# FTDI_Breakoput_Board.net
KiCad netlist of a schematic drawn in EAGLE
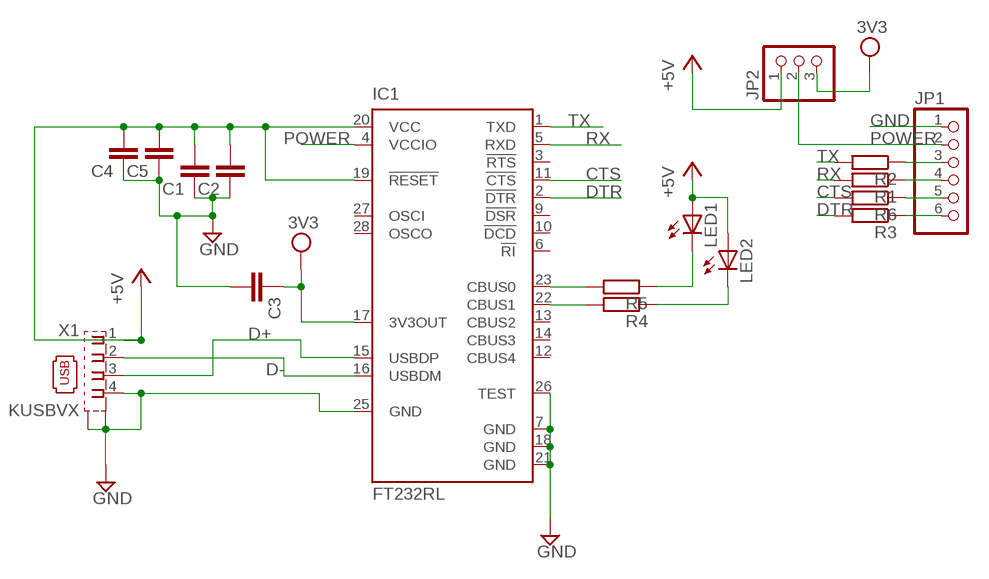
[diagram p0: schematic, sheet 1]

(export (version "E")
  (design (tool "Eeschema 10.0.6"))
  (components
    (comp (ref "C1")
      (value "C-EUC0805")
      (footprint "eagle-import:C0805")
      (libsource (lib "eagle-import") (part "C-EUC0805"))
    )
    (comp (ref "C2")
      (value "C-EUC0805")
      (footprint "eagle-import:C0805")
      (libsource (lib "eagle-import") (part "C-EUC0805"))
    )
    (comp (ref "C3")
      (value "C-EUC0805")
      (footprint "eagle-import:C0805")
      (libsource (lib "eagle-import") (part "C-EUC0805"))
    )
    (comp (ref "C4")
      (value "C-EUC0805")
      (footprint "eagle-import:C0805")
      (libsource (lib "eagle-import") (part "C-EUC0805"))
    )
    (comp (ref "C5")
      (value "C-EUC0805")
      (footprint "eagle-import:C0805")
      (libsource (lib "eagle-import") (part "C-EUC0805"))
    )
    (comp (ref "IC1")
      (value "FT232RL")
      (footprint "eagle-import:SSOP28")
      (libsource (lib "eagle-import") (part "FT232RL"))
    )
    (comp (ref "JP1")
      (value "PINHD-1X6")
      (footprint "eagle-import:1X06")
      (libsource (lib "eagle-import") (part "PINHD-1X6"))
    )
    (comp (ref "JP2")
      (value "PINHD-1X3")
      (footprint "eagle-import:1X03")
      (libsource (lib "eagle-import") (part "PINHD-1X3"))
    )
    (comp (ref "LED1")
      (value "LEDSML0805")
      (footprint "eagle-import:SML0805")
      (libsource (lib "eagle-import") (part "LEDSML0805"))
    )
    (comp (ref "LED2")
      (value "LEDSML0805")
      (footprint "eagle-import:SML0805")
      (libsource (lib "eagle-import") (part "LEDSML0805"))
    )
    (comp (ref "R1")
      (value "R-EU_R0805")
      (footprint "eagle-import:R0805")
      (libsource (lib "eagle-import") (part "R-EU_R0805"))
    )
    (comp (ref "R2")
      (value "R-EU_R0805")
      (footprint "eagle-import:R0805")
      (libsource (lib "eagle-import") (part "R-EU_R0805"))
    )
    (comp (ref "R3")
      (value "R-EU_R0805")
      (footprint "eagle-import:R0805")
      (libsource (lib "eagle-import") (part "R-EU_R0805"))
    )
    (comp (ref "R4")
      (value "R-EU_R0805")
      (footprint "eagle-import:R0805")
      (libsource (lib "eagle-import") (part "R-EU_R0805"))
    )
    (comp (ref "R5")
      (value "R-EU_R0805")
      (footprint "eagle-import:R0805")
      (libsource (lib "eagle-import") (part "R-EU_R0805"))
    )
    (comp (ref "R6")
      (value "R-EU_R0805")
      (footprint "eagle-import:R0805")
      (libsource (lib "eagle-import") (part "R-EU_R0805"))
    )
    (comp (ref "X1")
      (value "KUSBVX")
      (footprint "eagle-import:KUSBVX")
      (libsource (lib "eagle-import") (part "KUSBVX"))
    )
  )
  (nets
    (net (code "1") (name "+5V") (class "Default")
      (node (ref "C1") (pin "2") (pinfunction "2_2") (pintype "passive"))
      (node (ref "C2") (pin "2") (pinfunction "2_2") (pintype "passive"))
      (node (ref "C4") (pin "2") (pinfunction "2_2") (pintype "passive"))
      (node (ref "C5") (pin "2") (pinfunction "2_2") (pintype "passive"))
      (node (ref "IC1") (pin "19") (pinfunction "~{RESET}_19") (pintype "input"))
      (node (ref "IC1") (pin "20") (pinfunction "VCC_20") (pintype "power_in"))
      (node (ref "JP2") (pin "1") (pinfunction "1_1") (pintype "passive"))
      (node (ref "LED1") (pin "A") (pinfunction "A_A") (pintype "passive"))
      (node (ref "LED2") (pin "A") (pinfunction "A_A") (pintype "passive"))
      (node (ref "X1") (pin "1") (pinfunction "1_1") (pintype "passive"))
    )
    (net (code "2") (name "/CTS") (class "Default")
      (node (ref "IC1") (pin "11") (pinfunction "~{CTS}_11") (pintype "input"))
      (node (ref "R6") (pin "2") (pinfunction "2_2") (pintype "passive"))
    )
    (net (code "3") (name "/D+") (class "Default")
      (node (ref "IC1") (pin "15") (pinfunction "USBDP_15") (pintype "bidirectional"))
      (node (ref "X1") (pin "3") (pinfunction "3_3") (pintype "passive"))
    )
    (net (code "4") (name "/D-") (class "Default")
      (node (ref "IC1") (pin "16") (pinfunction "USBDM_16") (pintype "bidirectional"))
      (node (ref "X1") (pin "2") (pinfunction "2_2") (pintype "passive"))
    )
    (net (code "5") (name "/DTR") (class "Default")
      (node (ref "IC1") (pin "2") (pinfunction "~{DTR}_2") (pintype "output"))
      (node (ref "R3") (pin "2") (pinfunction "2_2") (pintype "passive"))
    )
    (net (code "6") (name "/POWER") (class "Default")
      (node (ref "IC1") (pin "4") (pinfunction "VCCIO_4") (pintype "power_in"))
      (node (ref "JP1") (pin "2") (pinfunction "2_2") (pintype "passive"))
      (node (ref "JP2") (pin "2") (pinfunction "2_2") (pintype "passive"))
    )
    (net (code "7") (name "/RX") (class "Default")
      (node (ref "IC1") (pin "5") (pinfunction "RXD_5") (pintype "input"))
      (node (ref "R1") (pin "2") (pinfunction "2_2") (pintype "passive"))
    )
    (net (code "8") (name "/TX") (class "Default")
      (node (ref "IC1") (pin "1") (pinfunction "TXD_1") (pintype "output"))
      (node (ref "R2") (pin "2") (pinfunction "2_2") (pintype "passive"))
    )
    (net (code "9") (name "3V3") (class "Default")
      (node (ref "C3") (pin "1") (pinfunction "1_1") (pintype "passive"))
      (node (ref "IC1") (pin "17") (pinfunction "3V3OUT_17") (pintype "output"))
      (node (ref "JP2") (pin "3") (pinfunction "3_3") (pintype "passive"))
    )
    (net (code "10") (name "GND") (class "Default")
      (node (ref "C1") (pin "1") (pinfunction "1_1") (pintype "passive"))
      (node (ref "C2") (pin "1") (pinfunction "1_1") (pintype "passive"))
      (node (ref "C3") (pin "2") (pinfunction "2_2") (pintype "passive"))
      (node (ref "C4") (pin "1") (pinfunction "1_1") (pintype "passive"))
      (node (ref "C5") (pin "1") (pinfunction "1_1") (pintype "passive"))
      (node (ref "IC1") (pin "18") (pinfunction "GND_18") (pintype "power_in"))
      (node (ref "IC1") (pin "21") (pinfunction "GND_21") (pintype "power_in"))
      (node (ref "IC1") (pin "25") (pinfunction "GND_25") (pintype "power_in"))
      (node (ref "IC1") (pin "26") (pinfunction "TEST_26") (pintype "input"))
      (node (ref "IC1") (pin "7") (pinfunction "GND_7") (pintype "power_in"))
      (node (ref "JP1") (pin "1") (pinfunction "1_1") (pintype "passive"))
      (node (ref "X1") (pin "4") (pinfunction "4_4") (pintype "passive"))
      (node (ref "X1") (pin "M1") (pinfunction "S1_M1") (pintype "passive"))
      (node (ref "X1") (pin "M2") (pinfunction "S2_M2") (pintype "passive"))
    )
    (net (code "11") (name "Net-(IC1-CBUS0)") (class "Default")
      (node (ref "IC1") (pin "23") (pinfunction "CBUS0_23") (pintype "bidirectional"))
      (node (ref "R5") (pin "2") (pinfunction "2_2") (pintype "passive"))
    )
    (net (code "12") (name "Net-(IC1-CBUS1)") (class "Default")
      (node (ref "IC1") (pin "22") (pinfunction "CBUS1_22") (pintype "bidirectional"))
      (node (ref "R4") (pin "2") (pinfunction "2_2") (pintype "passive"))
    )
    (net (code "13") (name "Net-(JP1-Pad3)") (class "Default")
      (node (ref "JP1") (pin "3") (pinfunction "3_3") (pintype "passive"))
      (node (ref "R2") (pin "1") (pinfunction "1_1") (pintype "passive"))
    )
    (net (code "14") (name "Net-(JP1-Pad4)") (class "Default")
      (node (ref "JP1") (pin "4") (pinfunction "4_4") (pintype "passive"))
      (node (ref "R1") (pin "1") (pinfunction "1_1") (pintype "passive"))
    )
    (net (code "15") (name "Net-(JP1-Pad5)") (class "Default")
      (node (ref "JP1") (pin "5") (pinfunction "5_5") (pintype "passive"))
      (node (ref "R6") (pin "1") (pinfunction "1_1") (pintype "passive"))
    )
    (net (code "16") (name "Net-(JP1-Pad6)") (class "Default")
      (node (ref "JP1") (pin "6") (pinfunction "6_6") (pintype "passive"))
      (node (ref "R3") (pin "1") (pinfunction "1_1") (pintype "passive"))
    )
    (net (code "17") (name "Net-(LED1-PadC)") (class "Default")
      (node (ref "LED1") (pin "C") (pinfunction "C_C") (pintype "passive"))
      (node (ref "R5") (pin "1") (pinfunction "1_1") (pintype "passive"))
    )
    (net (code "18") (name "Net-(LED2-PadC)") (class "Default")
      (node (ref "LED2") (pin "C") (pinfunction "C_C") (pintype "passive"))
      (node (ref "R4") (pin "1") (pinfunction "1_1") (pintype "passive"))
    )
    (net (code "19") (name "unconnected-(IC1-CBUS2-Pad13)") (class "Default")
      (node (ref "IC1") (pin "13") (pinfunction "CBUS2_13") (pintype "bidirectional"))
    )
    (net (code "20") (name "unconnected-(IC1-CBUS3-Pad14)") (class "Default")
      (node (ref "IC1") (pin "14") (pinfunction "CBUS3_14") (pintype "bidirectional"))
    )
    (net (code "21") (name "unconnected-(IC1-CBUS4-Pad12)") (class "Default")
      (node (ref "IC1") (pin "12") (pinfunction "CBUS4_12") (pintype "bidirectional"))
    )
    (net (code "22") (name "unconnected-(IC1-OSCI-Pad27)") (class "Default")
      (node (ref "IC1") (pin "27") (pinfunction "OSCI_27") (pintype "input"))
    )
    (net (code "23") (name "unconnected-(IC1-OSCO-Pad28)") (class "Default")
      (node (ref "IC1") (pin "28") (pinfunction "OSCO_28") (pintype "output"))
    )
    (net (code "24") (name "unconnected-(IC1-~{DCD}-Pad10)") (class "Default")
      (node (ref "IC1") (pin "10") (pinfunction "~{DCD}_10") (pintype "input"))
    )
    (net (code "25") (name "unconnected-(IC1-~{DSR}-Pad9)") (class "Default")
      (node (ref "IC1") (pin "9") (pinfunction "~{DSR}_9") (pintype "input"))
    )
    (net (code "26") (name "unconnected-(IC1-~{RI}-Pad6)") (class "Default")
      (node (ref "IC1") (pin "6") (pinfunction "~{RI}_6") (pintype "input"))
    )
    (net (code "27") (name "unconnected-(IC1-~{RTS}-Pad3)") (class "Default")
      (node (ref "IC1") (pin "3") (pinfunction "~{RTS}_3") (pintype "output"))
    )
  )
)
